# Power.net
KiCad netlist of a schematic drawn in Altium Designer
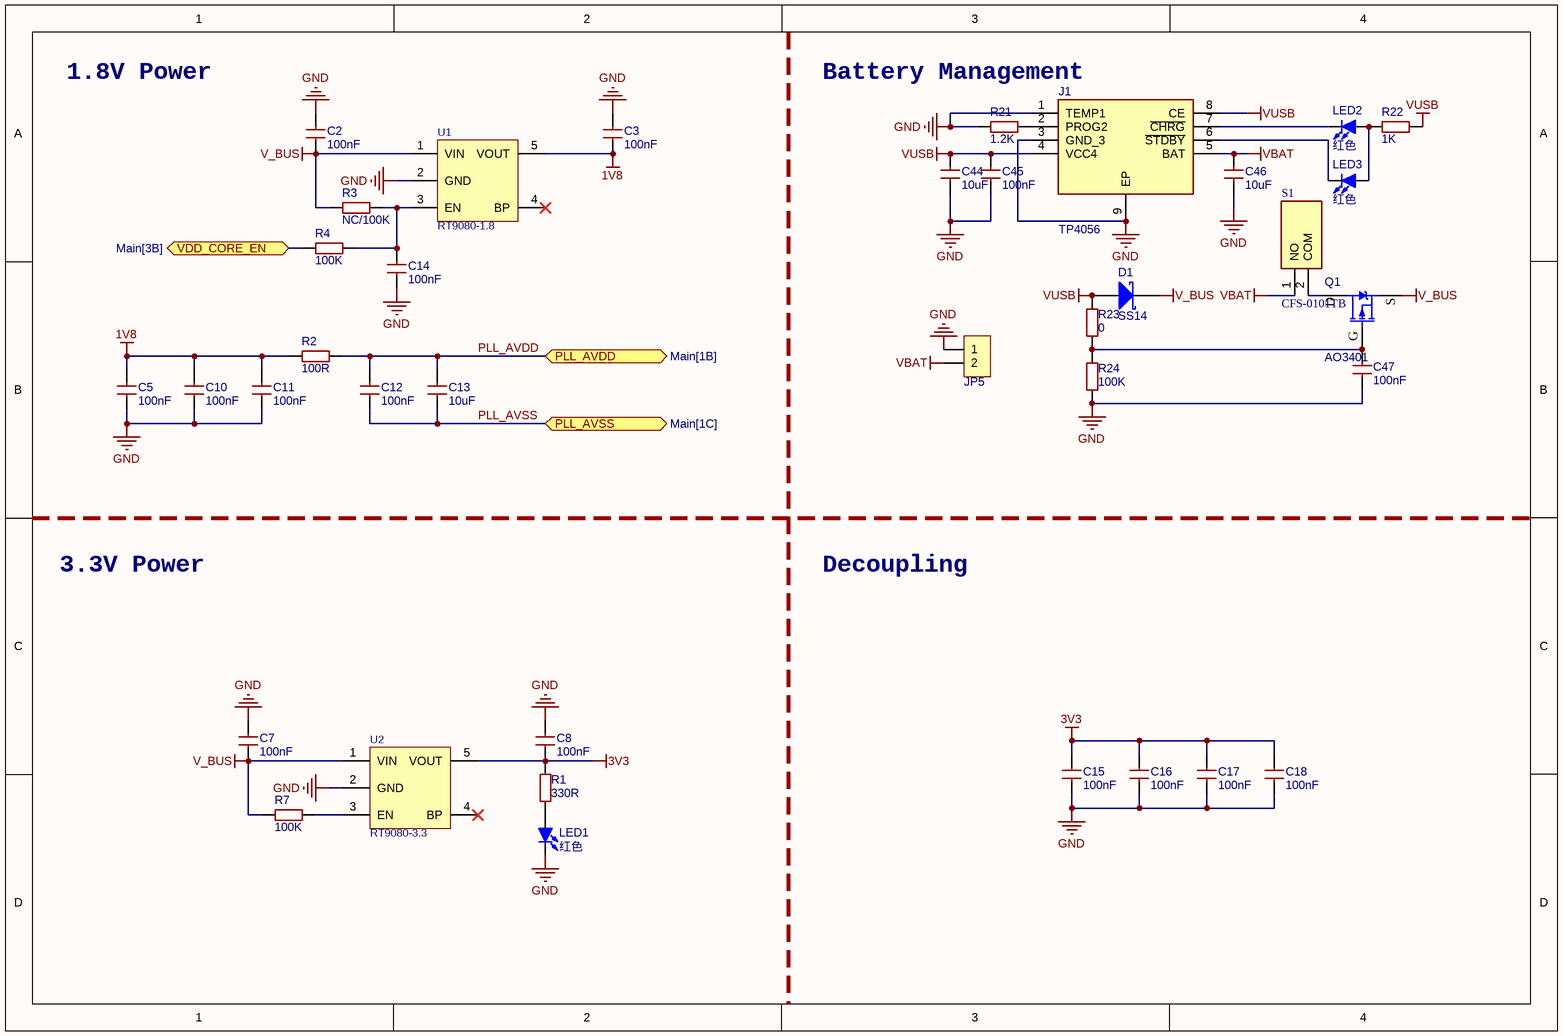
[diagram p0: Power.SchDoc]

(export (version "E")
  (design (tool "Eeschema 10.0.6"))
  (components
    (comp (ref "C2")
      (value "100nF")
      (footprint "C0603_NS")
      (description "贴片电容/MLCC电容")
      (libsource (lib "0.1 - 电阻-电容-电感-晶振-晶体-磁珠-电位器-法拉电容-馈通电容") (part "C"))
    )
    (comp (ref "C3")
      (value "100nF")
      (footprint "C0603_NS")
      (description "贴片电容/MLCC电容")
      (libsource (lib "0.1 - 电阻-电容-电感-晶振-晶体-磁珠-电位器-法拉电容-馈通电容") (part "C"))
    )
    (comp (ref "C5")
      (value "100nF")
      (footprint "C0603_NS")
      (description "贴片电容/MLCC电容")
      (libsource (lib "0.1 - 电阻-电容-电感-晶振-晶体-磁珠-电位器-法拉电容-馈通电容") (part "C"))
    )
    (comp (ref "C7")
      (value "100nF")
      (footprint "C0603_NS")
      (description "贴片电容/MLCC电容")
      (libsource (lib "0.1 - 电阻-电容-电感-晶振-晶体-磁珠-电位器-法拉电容-馈通电容") (part "C"))
    )
    (comp (ref "C8")
      (value "100nF")
      (footprint "C0603_NS")
      (description "贴片电容/MLCC电容")
      (libsource (lib "0.1 - 电阻-电容-电感-晶振-晶体-磁珠-电位器-法拉电容-馈通电容") (part "C"))
    )
    (comp (ref "C10")
      (value "100nF")
      (footprint "C0603_NS")
      (description "贴片电容/MLCC电容")
      (libsource (lib "0.1 - 电阻-电容-电感-晶振-晶体-磁珠-电位器-法拉电容-馈通电容") (part "C"))
    )
    (comp (ref "C11")
      (value "100nF")
      (footprint "C0603_NS")
      (description "贴片电容/MLCC电容")
      (libsource (lib "0.1 - 电阻-电容-电感-晶振-晶体-磁珠-电位器-法拉电容-馈通电容") (part "C"))
    )
    (comp (ref "C12")
      (value "100nF")
      (footprint "C0603_NS")
      (description "贴片电容/MLCC电容")
      (libsource (lib "0.1 - 电阻-电容-电感-晶振-晶体-磁珠-电位器-法拉电容-馈通电容") (part "C"))
    )
    (comp (ref "C13")
      (value "10uF")
      (footprint "C0603_NS")
      (description "贴片电容/MLCC电容")
      (libsource (lib "0.1 - 电阻-电容-电感-晶振-晶体-磁珠-电位器-法拉电容-馈通电容") (part "C"))
    )
    (comp (ref "C14")
      (value "100nF")
      (footprint "C0603_NS")
      (description "贴片电容/MLCC电容")
      (libsource (lib "0.1 - 电阻-电容-电感-晶振-晶体-磁珠-电位器-法拉电容-馈通电容") (part "C"))
    )
    (comp (ref "C15")
      (value "100nF")
      (footprint "C0603_NS")
      (description "贴片电容/MLCC电容")
      (libsource (lib "0.1 - 电阻-电容-电感-晶振-晶体-磁珠-电位器-法拉电容-馈通电容") (part "C"))
    )
    (comp (ref "C16")
      (value "100nF")
      (footprint "C0603_NS")
      (description "贴片电容/MLCC电容")
      (libsource (lib "0.1 - 电阻-电容-电感-晶振-晶体-磁珠-电位器-法拉电容-馈通电容") (part "C"))
    )
    (comp (ref "C17")
      (value "100nF")
      (footprint "C0603_NS")
      (description "贴片电容/MLCC电容")
      (libsource (lib "0.1 - 电阻-电容-电感-晶振-晶体-磁珠-电位器-法拉电容-馈通电容") (part "C"))
    )
    (comp (ref "C18")
      (value "100nF")
      (footprint "C0603_NS")
      (description "贴片电容/MLCC电容")
      (libsource (lib "0.1 - 电阻-电容-电感-晶振-晶体-磁珠-电位器-法拉电容-馈通电容") (part "C"))
    )
    (comp (ref "C44")
      (value "10uF")
      (footprint "C0603_NS")
      (description "贴片电容/MLCC电容")
      (libsource (lib "0.1 - 电阻-电容-电感-晶振-晶体-磁珠-电位器-法拉电容-馈通电容") (part "C"))
    )
    (comp (ref "C45")
      (value "100nF")
      (footprint "C0603_NS")
      (description "贴片电容/MLCC电容")
      (libsource (lib "0.1 - 电阻-电容-电感-晶振-晶体-磁珠-电位器-法拉电容-馈通电容") (part "C"))
    )
    (comp (ref "C46")
      (value "10uF")
      (footprint "C0603_NS")
      (description "贴片电容/MLCC电容")
      (libsource (lib "0.1 - 电阻-电容-电感-晶振-晶体-磁珠-电位器-法拉电容-馈通电容") (part "C"))
    )
    (comp (ref "C47")
      (value "100nF")
      (footprint "C0603_NS")
      (description "贴片电容/MLCC电容")
      (libsource (lib "0.1 - 电阻-电容-电感-晶振-晶体-磁珠-电位器-法拉电容-馈通电容") (part "C"))
    )
    (comp (ref "D1")
      (value "SS14")
      (footprint "SMA")
      (description "肖特基二极管")
      (libsource (lib "0.2 - 二极管-TVS-ESD-整流桥-放电管") (part "SS14"))
    )
    (comp (ref "J1")
      (value "TP4056")
      (footprint "SamacSys:SOIC127P600X175-9N")
      (description "Connector")
      (libsource (lib "*") (part "TP4056"))
    )
    (comp (ref "JP5")
      (value "HDR-1X2")
      (footprint "XH2.54-LS-2P")
      (description "2P接插件")
      (libsource (lib "5.5 - 2.54mm连接器(KF2EDGK_XH2.54_2.54排针排母)") (part "Header 2"))
    )
    (comp (ref "LED1")
      (value "红色")
      (footprint "LED0603_R")
      (description "贴片LED")
      (libsource (lib "0.3 - LED发光二极管-IR二极管_接收管-光耦") (part "LED-SMD"))
    )
    (comp (ref "LED2")
      (value "红色")
      (footprint "LED0603_R")
      (description "贴片LED")
      (libsource (lib "0.3 - LED发光二极管-IR二极管_接收管-光耦") (part "LED-SMD"))
    )
    (comp (ref "LED3")
      (value "红色")
      (footprint "LED0603_R")
      (description "贴片LED")
      (libsource (lib "0.3 - LED发光二极管-IR二极管_接收管-光耦") (part "LED-SMD"))
    )
    (comp (ref "Q1")
      (value "AO3401")
      (footprint "SOT23-3N")
      (description "P沟道 30V/4.2A")
      (libsource (lib "0.4 - 三极管-场效应管-可控硅") (part "AO3401"))
    )
    (comp (ref "R1")
      (value "330R")
      (footprint "R0603_NS")
      (description "贴片电阻")
      (libsource (lib "") (part "R_2"))
    )
    (comp (ref "R2")
      (value "100R")
      (footprint "R0603_NS")
      (description "贴片电阻")
      (libsource (lib "0.1 - 电阻-电容-电感-晶振-晶体-磁珠-电位器-法拉电容-馈通电容") (part "R"))
    )
    (comp (ref "R3")
      (value "NC/100K")
      (footprint "R0603_NS")
      (description "贴片电阻")
      (libsource (lib "0.1 - 电阻-电容-电感-晶振-晶体-磁珠-电位器-法拉电容-馈通电容") (part "R"))
    )
    (comp (ref "R4")
      (value "100K")
      (footprint "R0603_NS")
      (description "贴片电阻")
      (libsource (lib "0.1 - 电阻-电容-电感-晶振-晶体-磁珠-电位器-法拉电容-馈通电容") (part "R"))
    )
    (comp (ref "R7")
      (value "100K")
      (footprint "R0603_NS")
      (description "贴片电阻")
      (libsource (lib "0.1 - 电阻-电容-电感-晶振-晶体-磁珠-电位器-法拉电容-馈通电容") (part "R"))
    )
    (comp (ref "R21")
      (value "1.2K")
      (footprint "R0603_NS")
      (description "贴片电阻")
      (libsource (lib "0.1 - 电阻-电容-电感-晶振-晶体-磁珠-电位器-法拉电容-馈通电容") (part "R"))
    )
    (comp (ref "R22")
      (value "1K")
      (footprint "R0603_NS")
      (description "贴片电阻")
      (libsource (lib "0.1 - 电阻-电容-电感-晶振-晶体-磁珠-电位器-法拉电容-馈通电容") (part "R"))
    )
    (comp (ref "R23")
      (value "0")
      (footprint "R0603_NS")
      (description "贴片电阻")
      (libsource (lib "") (part "R_1"))
    )
    (comp (ref "R24")
      (value "100K")
      (footprint "R0603_NS")
      (description "贴片电阻")
      (libsource (lib "") (part "R_1"))
    )
    (comp (ref "S1")
      (value "CFS-0101TB")
      (footprint "SamacSys:CFS0101TB")
      (description "Switch")
      (fields (field (name "MOUSER PART NUMBER") "229-CFS-0101TB"))
      (libsource (lib "*") (part "CFS-0101TB"))
    )
    (comp (ref "U1")
      (value "RT9080-1.8")
      (footprint "SOT-23-5")
      (description "LDO 1.8V/0.3A")
      (libsource (lib "0.7 - 电源类芯片") (part "RT9193-18GB"))
    )
    (comp (ref "U2")
      (value "RT9080-3.3")
      (footprint "SOT-23-5")
      (description "LDO 1.8V/0.3A")
      (libsource (lib "0.7 - 电源类芯片") (part "RT9193-18GB"))
    )
  )
  (nets
    (net (code "1") (name "/PLL_AVDD") (class "Default")
      (node (ref "C12") (pin "2") (pinfunction "2_2") (pintype "passive"))
      (node (ref "C13") (pin "2") (pinfunction "2_2") (pintype "passive"))
      (node (ref "R2") (pin "2") (pinfunction "2_2") (pintype "passive"))
    )
    (net (code "2") (name "/PLL_AVSS") (class "Default")
      (node (ref "C12") (pin "1") (pinfunction "1_1") (pintype "passive"))
      (node (ref "C13") (pin "1") (pinfunction "1_1") (pintype "passive"))
    )
    (net (code "3") (name "/VDD_CORE_EN") (class "Default")
      (node (ref "R4") (pin "1") (pinfunction "1_1") (pintype "passive"))
    )
    (net (code "4") (name "1V8") (class "Default")
      (node (ref "C10") (pin "1") (pinfunction "1_1") (pintype "passive"))
      (node (ref "C11") (pin "2") (pinfunction "2_2") (pintype "passive"))
      (node (ref "C3") (pin "1") (pinfunction "1_1") (pintype "passive"))
      (node (ref "C5") (pin "2") (pinfunction "2_2") (pintype "passive"))
      (node (ref "R2") (pin "1") (pinfunction "1_1") (pintype "passive"))
      (node (ref "U1") (pin "5") (pinfunction "VOUT_5") (pintype "passive"))
    )
    (net (code "5") (name "3V3") (class "Default")
      (node (ref "C15") (pin "2") (pinfunction "2_2") (pintype "passive"))
      (node (ref "C16") (pin "2") (pinfunction "2_2") (pintype "passive"))
      (node (ref "C17") (pin "2") (pinfunction "2_2") (pintype "passive"))
      (node (ref "C18") (pin "2") (pinfunction "2_2") (pintype "passive"))
      (node (ref "C8") (pin "1") (pinfunction "1_1") (pintype "passive"))
      (node (ref "R1") (pin "1") (pinfunction "1_1") (pintype "passive"))
      (node (ref "U2") (pin "5") (pinfunction "VOUT_5") (pintype "passive"))
    )
    (net (code "6") (name "GND") (class "Default")
      (node (ref "C10") (pin "2") (pinfunction "2_2") (pintype "passive"))
      (node (ref "C11") (pin "1") (pinfunction "1_1") (pintype "passive"))
      (node (ref "C14") (pin "1") (pinfunction "1_1") (pintype "passive"))
      (node (ref "C15") (pin "1") (pinfunction "1_1") (pintype "passive"))
      (node (ref "C16") (pin "1") (pinfunction "1_1") (pintype "passive"))
      (node (ref "C17") (pin "1") (pinfunction "1_1") (pintype "passive"))
      (node (ref "C18") (pin "1") (pinfunction "1_1") (pintype "passive"))
      (node (ref "C2") (pin "2") (pinfunction "2_2") (pintype "passive"))
      (node (ref "C3") (pin "2") (pinfunction "2_2") (pintype "passive"))
      (node (ref "C44") (pin "1") (pinfunction "1_1") (pintype "passive"))
      (node (ref "C45") (pin "1") (pinfunction "1_1") (pintype "passive"))
      (node (ref "C46") (pin "1") (pinfunction "1_1") (pintype "passive"))
      (node (ref "C47") (pin "1") (pinfunction "1_1") (pintype "passive"))
      (node (ref "C5") (pin "1") (pinfunction "1_1") (pintype "passive"))
      (node (ref "C7") (pin "2") (pinfunction "2_2") (pintype "passive"))
      (node (ref "C8") (pin "2") (pinfunction "2_2") (pintype "passive"))
      (node (ref "J1") (pin "1") (pinfunction "TEMP1_1") (pintype "passive"))
      (node (ref "J1") (pin "3") (pinfunction "GND_3_3") (pintype "passive"))
      (node (ref "J1") (pin "9") (pinfunction "EP_9") (pintype "passive"))
      (node (ref "JP5") (pin "1") (pinfunction "1_1") (pintype "passive"))
      (node (ref "LED1") (pin "2") (pinfunction "K_2") (pintype "passive"))
      (node (ref "R21") (pin "1") (pinfunction "1_1") (pintype "passive"))
      (node (ref "R24") (pin "1") (pinfunction "1_1") (pintype "passive"))
      (node (ref "U1") (pin "2") (pinfunction "GND_2") (pintype "passive"))
      (node (ref "U2") (pin "2") (pinfunction "GND_2") (pintype "passive"))
    )
    (net (code "7") (name "Net-(J1-PROG2)") (class "Default")
      (node (ref "J1") (pin "2") (pinfunction "PROG2_2") (pintype "passive"))
      (node (ref "R21") (pin "2") (pinfunction "2_2") (pintype "passive"))
    )
    (net (code "8") (name "Net-(J1-~{CHRG})") (class "Default")
      (node (ref "J1") (pin "7") (pinfunction "~{CHRG}_7") (pintype "passive"))
      (node (ref "LED2") (pin "2") (pinfunction "K_2") (pintype "passive"))
    )
    (net (code "9") (name "Net-(J1-~{STDBY})") (class "Default")
      (node (ref "J1") (pin "6") (pinfunction "~{STDBY}_6") (pintype "passive"))
      (node (ref "LED3") (pin "2") (pinfunction "K_2") (pintype "passive"))
    )
    (net (code "10") (name "Net-(LED1-A)") (class "Default")
      (node (ref "LED1") (pin "1") (pinfunction "A_1") (pintype "passive"))
      (node (ref "R1") (pin "2") (pinfunction "2_2") (pintype "passive"))
    )
    (net (code "11") (name "Net-(LED2-A)") (class "Default")
      (node (ref "LED2") (pin "1") (pinfunction "A_1") (pintype "passive"))
      (node (ref "LED3") (pin "1") (pinfunction "A_1") (pintype "passive"))
      (node (ref "R22") (pin "1") (pinfunction "1_1") (pintype "passive"))
    )
    (net (code "12") (name "Net-(Q1-D)") (class "Default")
      (node (ref "Q1") (pin "3") (pinfunction "D_3") (pintype "passive"))
      (node (ref "S1") (pin "2") (pinfunction "COM_2") (pintype "passive"))
    )
    (net (code "13") (name "Net-(Q1-G)") (class "Default")
      (node (ref "C47") (pin "2") (pinfunction "2_2") (pintype "passive"))
      (node (ref "Q1") (pin "1") (pinfunction "G_1") (pintype "passive"))
      (node (ref "R23") (pin "1") (pinfunction "1_1") (pintype "passive"))
      (node (ref "R24") (pin "2") (pinfunction "2_2") (pintype "passive"))
    )
    (net (code "14") (name "Net-(U1-EN)") (class "Default")
      (node (ref "C14") (pin "2") (pinfunction "2_2") (pintype "passive"))
      (node (ref "R3") (pin "2") (pinfunction "2_2") (pintype "passive"))
      (node (ref "R4") (pin "2") (pinfunction "2_2") (pintype "passive"))
      (node (ref "U1") (pin "3") (pinfunction "EN_3") (pintype "passive"))
    )
    (net (code "15") (name "Net-(U2-EN)") (class "Default")
      (node (ref "R7") (pin "2") (pinfunction "2_2") (pintype "passive"))
      (node (ref "U2") (pin "3") (pinfunction "EN_3") (pintype "passive"))
    )
    (net (code "16") (name "VBAT") (class "Default")
      (node (ref "C46") (pin "2") (pinfunction "2_2") (pintype "passive"))
      (node (ref "J1") (pin "5") (pinfunction "BAT_5") (pintype "passive"))
      (node (ref "JP5") (pin "2") (pinfunction "2_2") (pintype "passive"))
      (node (ref "S1") (pin "1") (pinfunction "NO_1") (pintype "passive"))
    )
    (net (code "17") (name "VUSB") (class "Default")
      (node (ref "C44") (pin "2") (pinfunction "2_2") (pintype "passive"))
      (node (ref "C45") (pin "2") (pinfunction "2_2") (pintype "passive"))
      (node (ref "D1") (pin "1") (pinfunction "A_1") (pintype "passive"))
      (node (ref "J1") (pin "4") (pinfunction "VCC4_4") (pintype "passive"))
      (node (ref "J1") (pin "8") (pinfunction "CE_8") (pintype "passive"))
      (node (ref "R22") (pin "2") (pinfunction "2_2") (pintype "passive"))
      (node (ref "R23") (pin "2") (pinfunction "2_2") (pintype "passive"))
    )
    (net (code "18") (name "V_BUS") (class "Default")
      (node (ref "C2") (pin "1") (pinfunction "1_1") (pintype "passive"))
      (node (ref "C7") (pin "1") (pinfunction "1_1") (pintype "passive"))
      (node (ref "D1") (pin "2") (pinfunction "K_2") (pintype "passive"))
      (node (ref "Q1") (pin "2") (pinfunction "S_2") (pintype "passive"))
      (node (ref "R3") (pin "1") (pinfunction "1_1") (pintype "passive"))
      (node (ref "R7") (pin "1") (pinfunction "1_1") (pintype "passive"))
      (node (ref "U1") (pin "1") (pinfunction "VIN_1") (pintype "passive"))
      (node (ref "U2") (pin "1") (pinfunction "VIN_1") (pintype "passive"))
    )
    (net (code "19") (name "unconnected-(U1-BP-Pad4)") (class "Default")
      (node (ref "U1") (pin "4") (pinfunction "BP_4") (pintype "passive+no_connect"))
    )
    (net (code "20") (name "unconnected-(U2-BP-Pad4)") (class "Default")
      (node (ref "U2") (pin "4") (pinfunction "BP_4") (pintype "passive+no_connect"))
    )
  )
)
